# RMP_-_HALF_BRIDGE_0_0_1.net
KiCad netlist of a schematic drawn in EAGLE
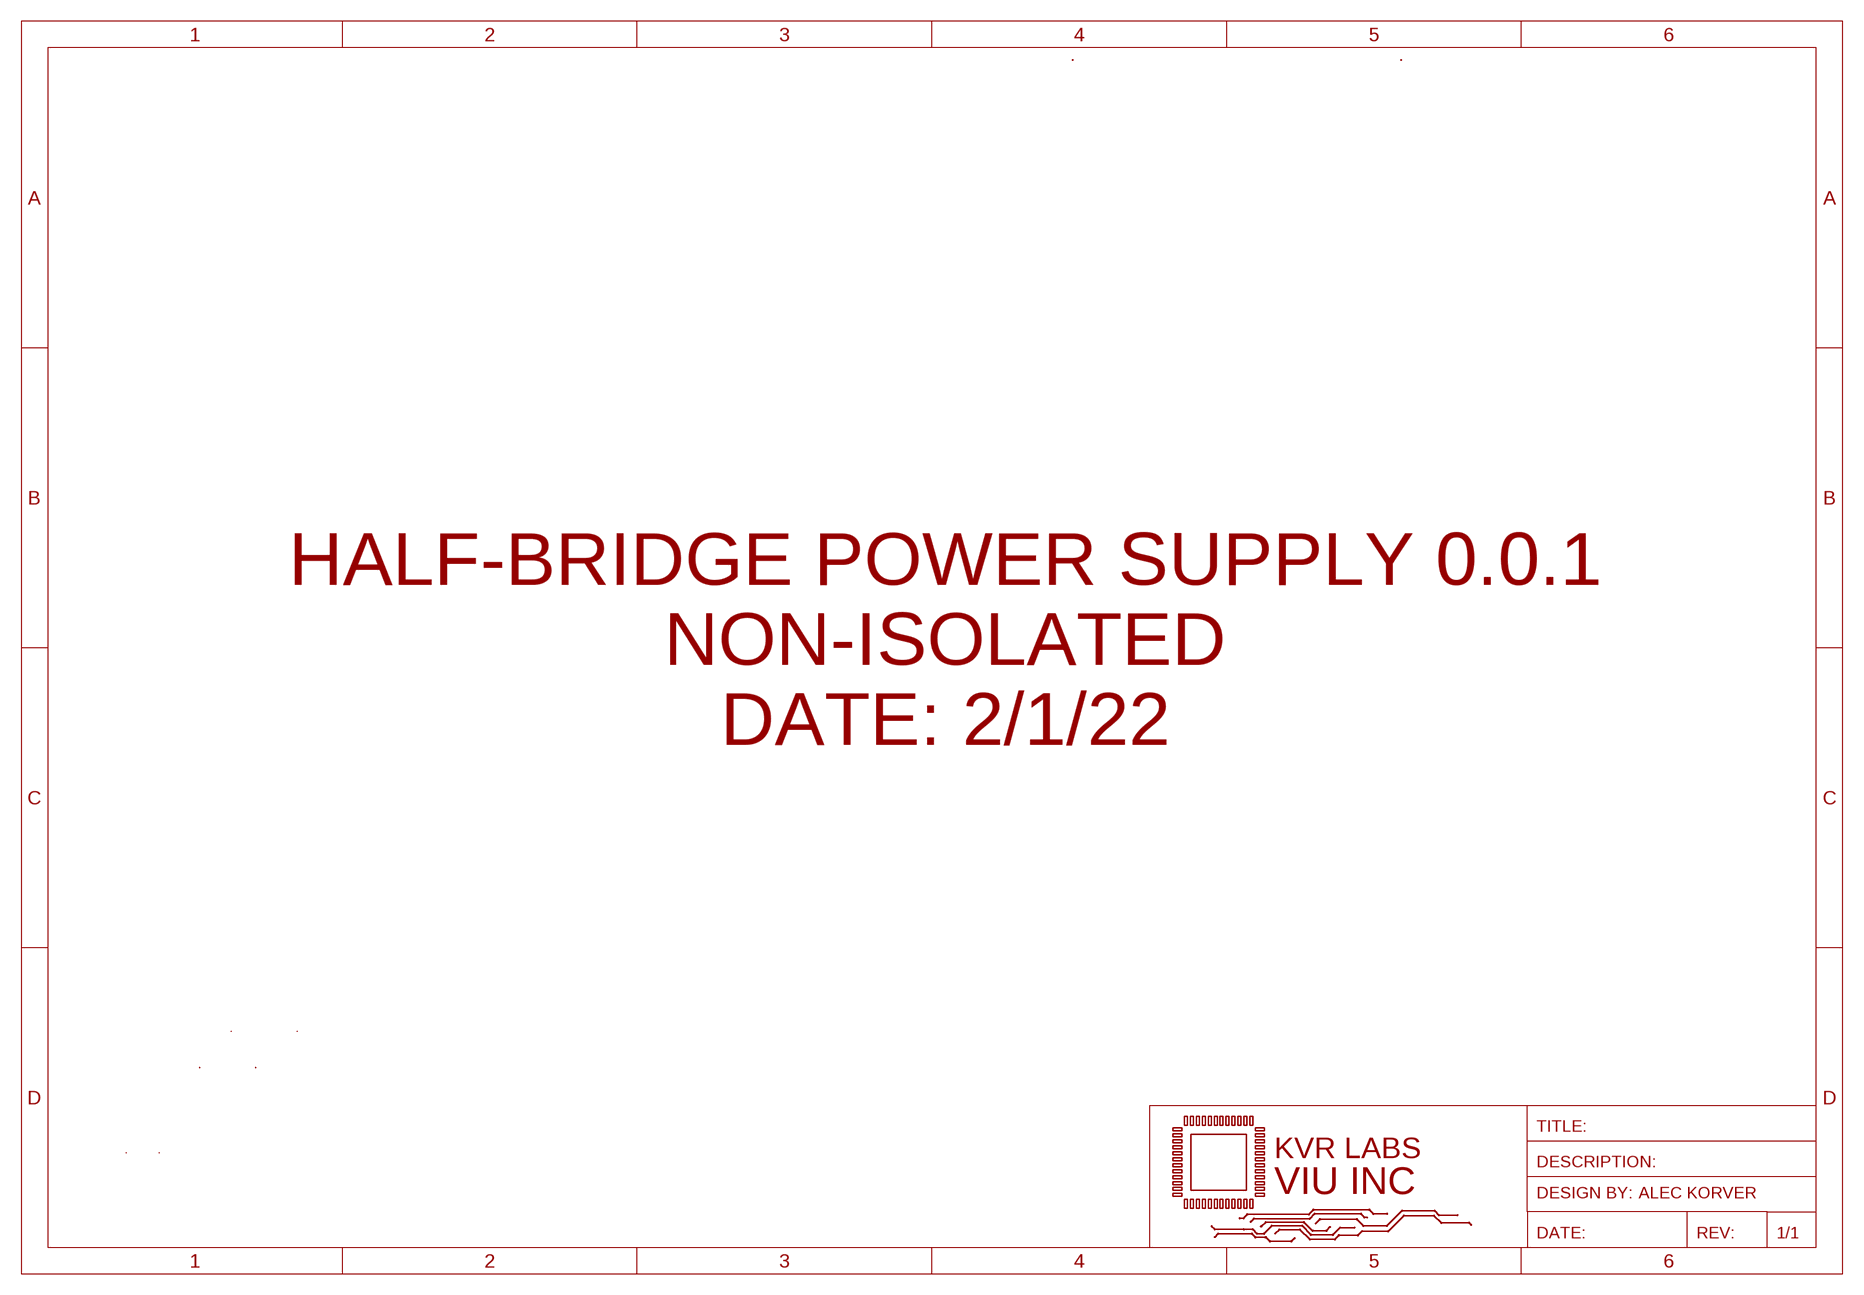
[diagram p0: schematic, sheet 1]
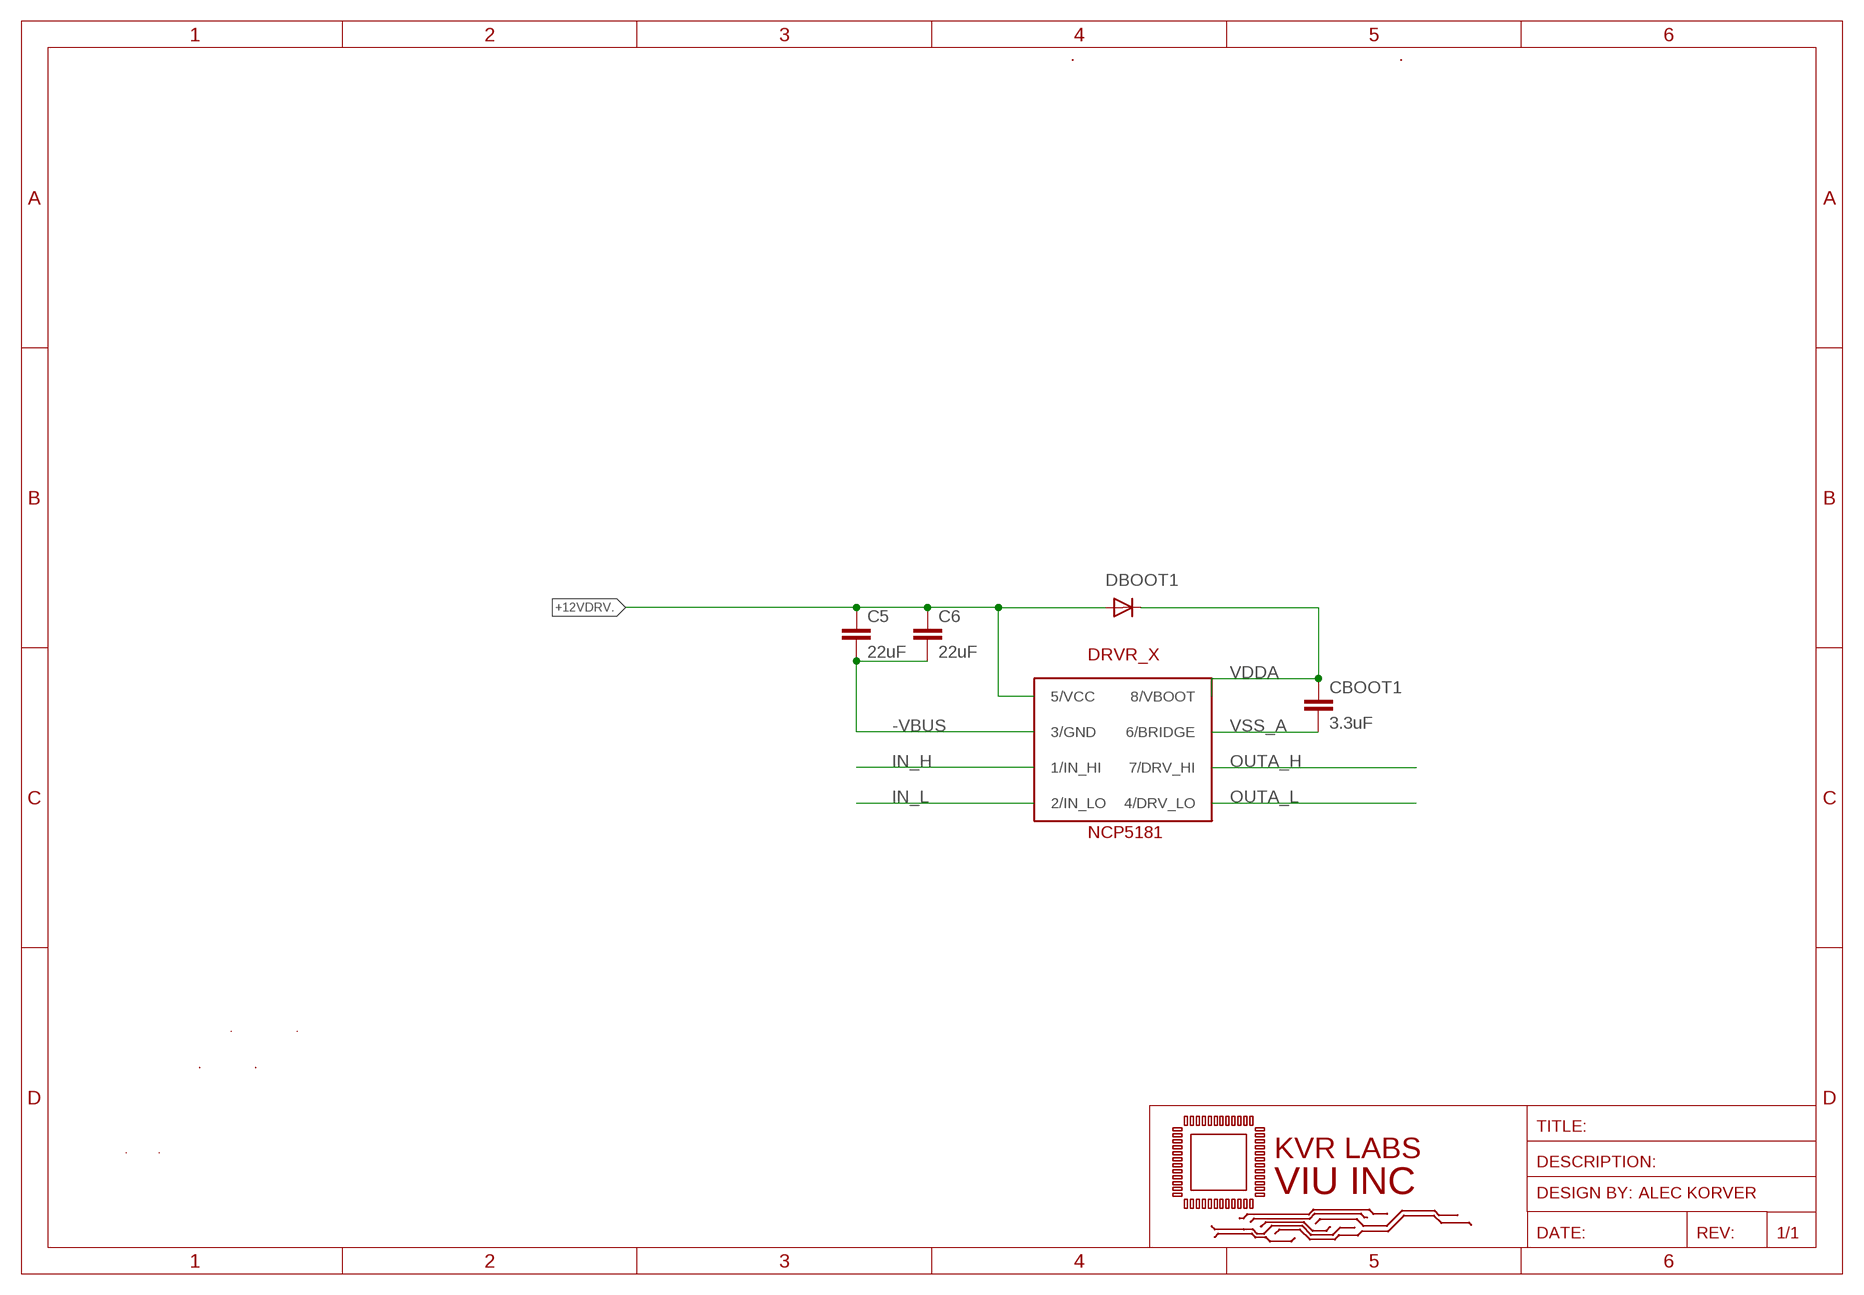
[diagram p1: schematic, sheet 2]
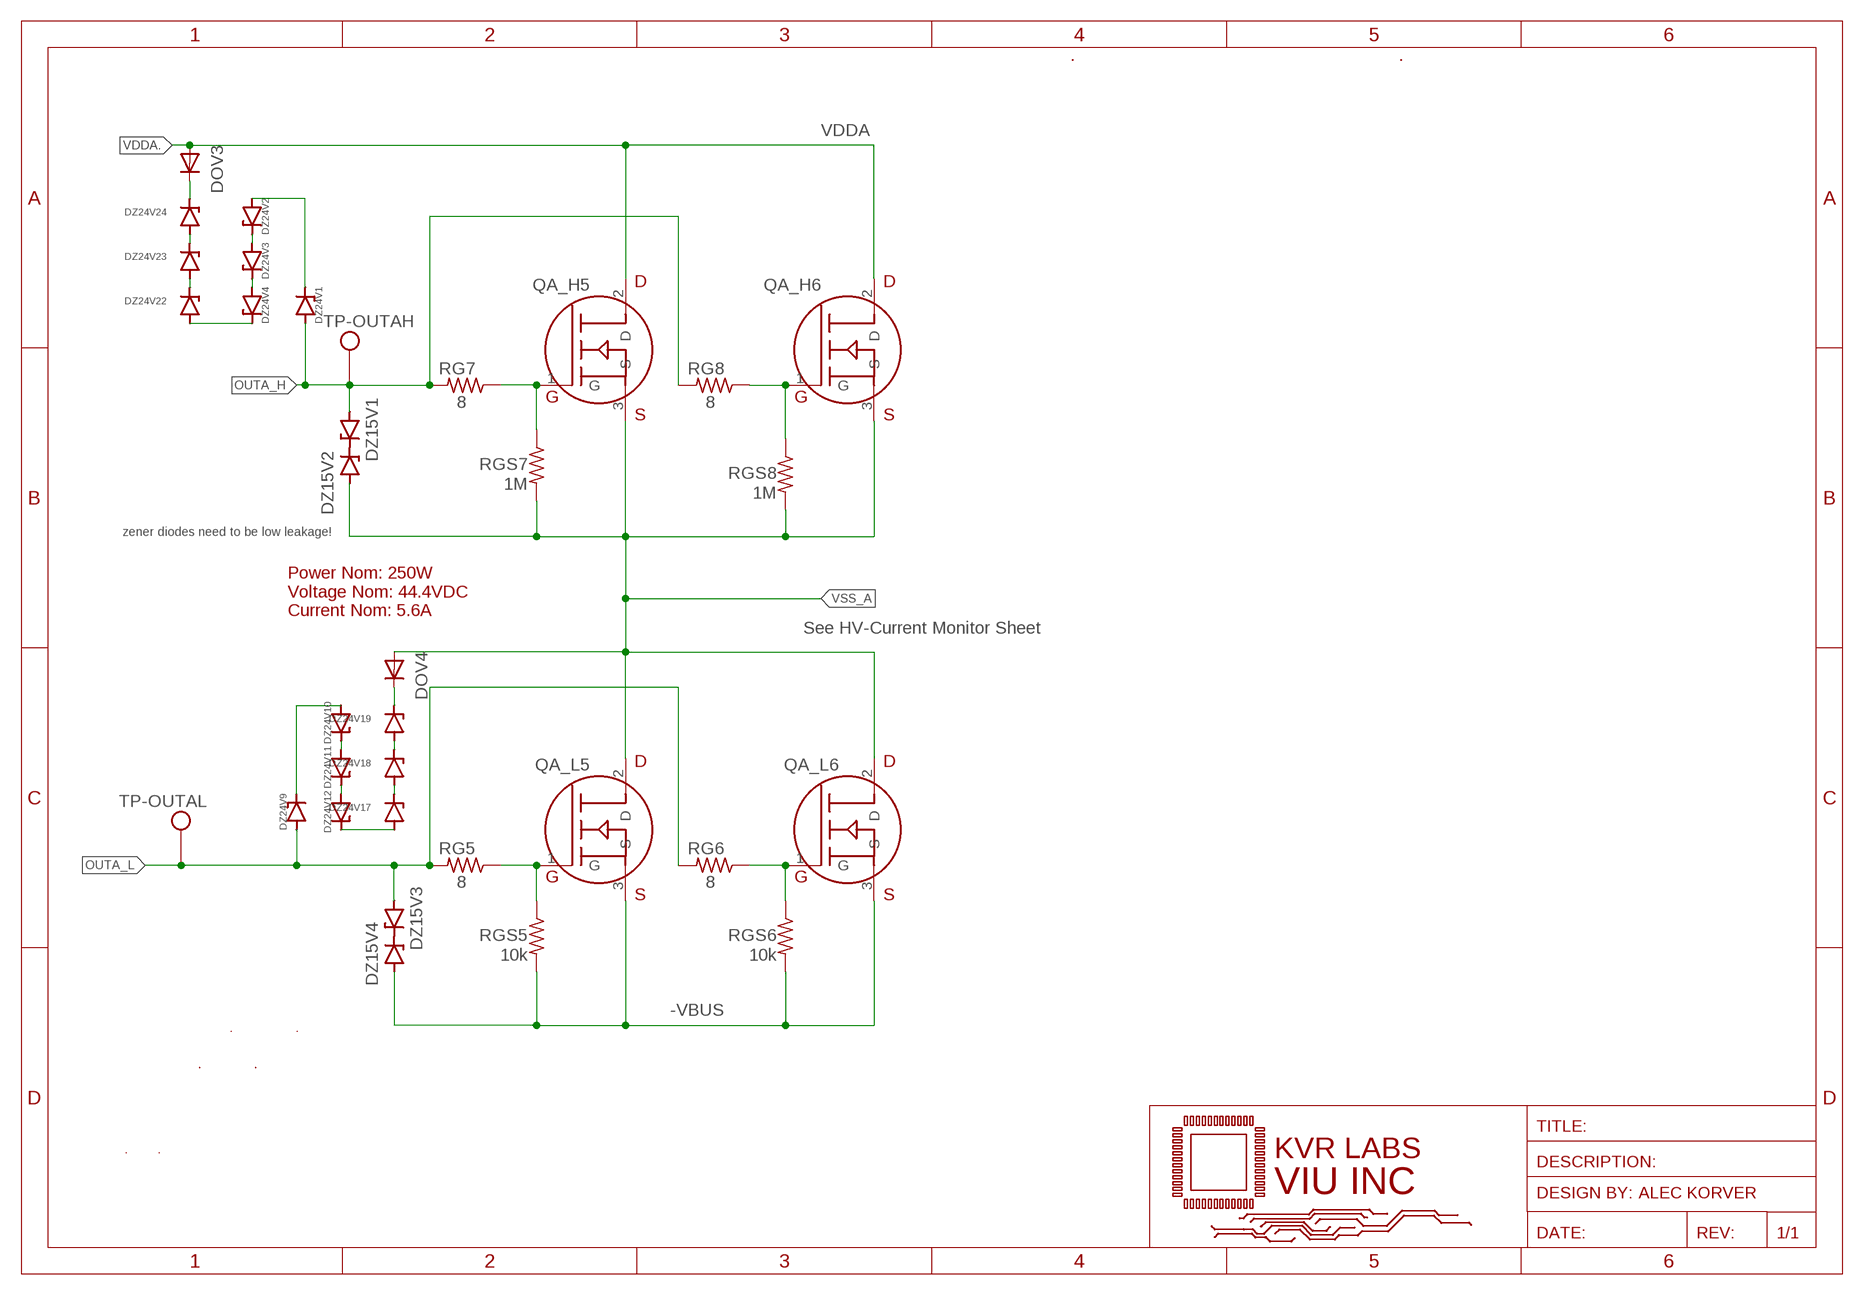
[diagram p2: schematic, sheet 3]
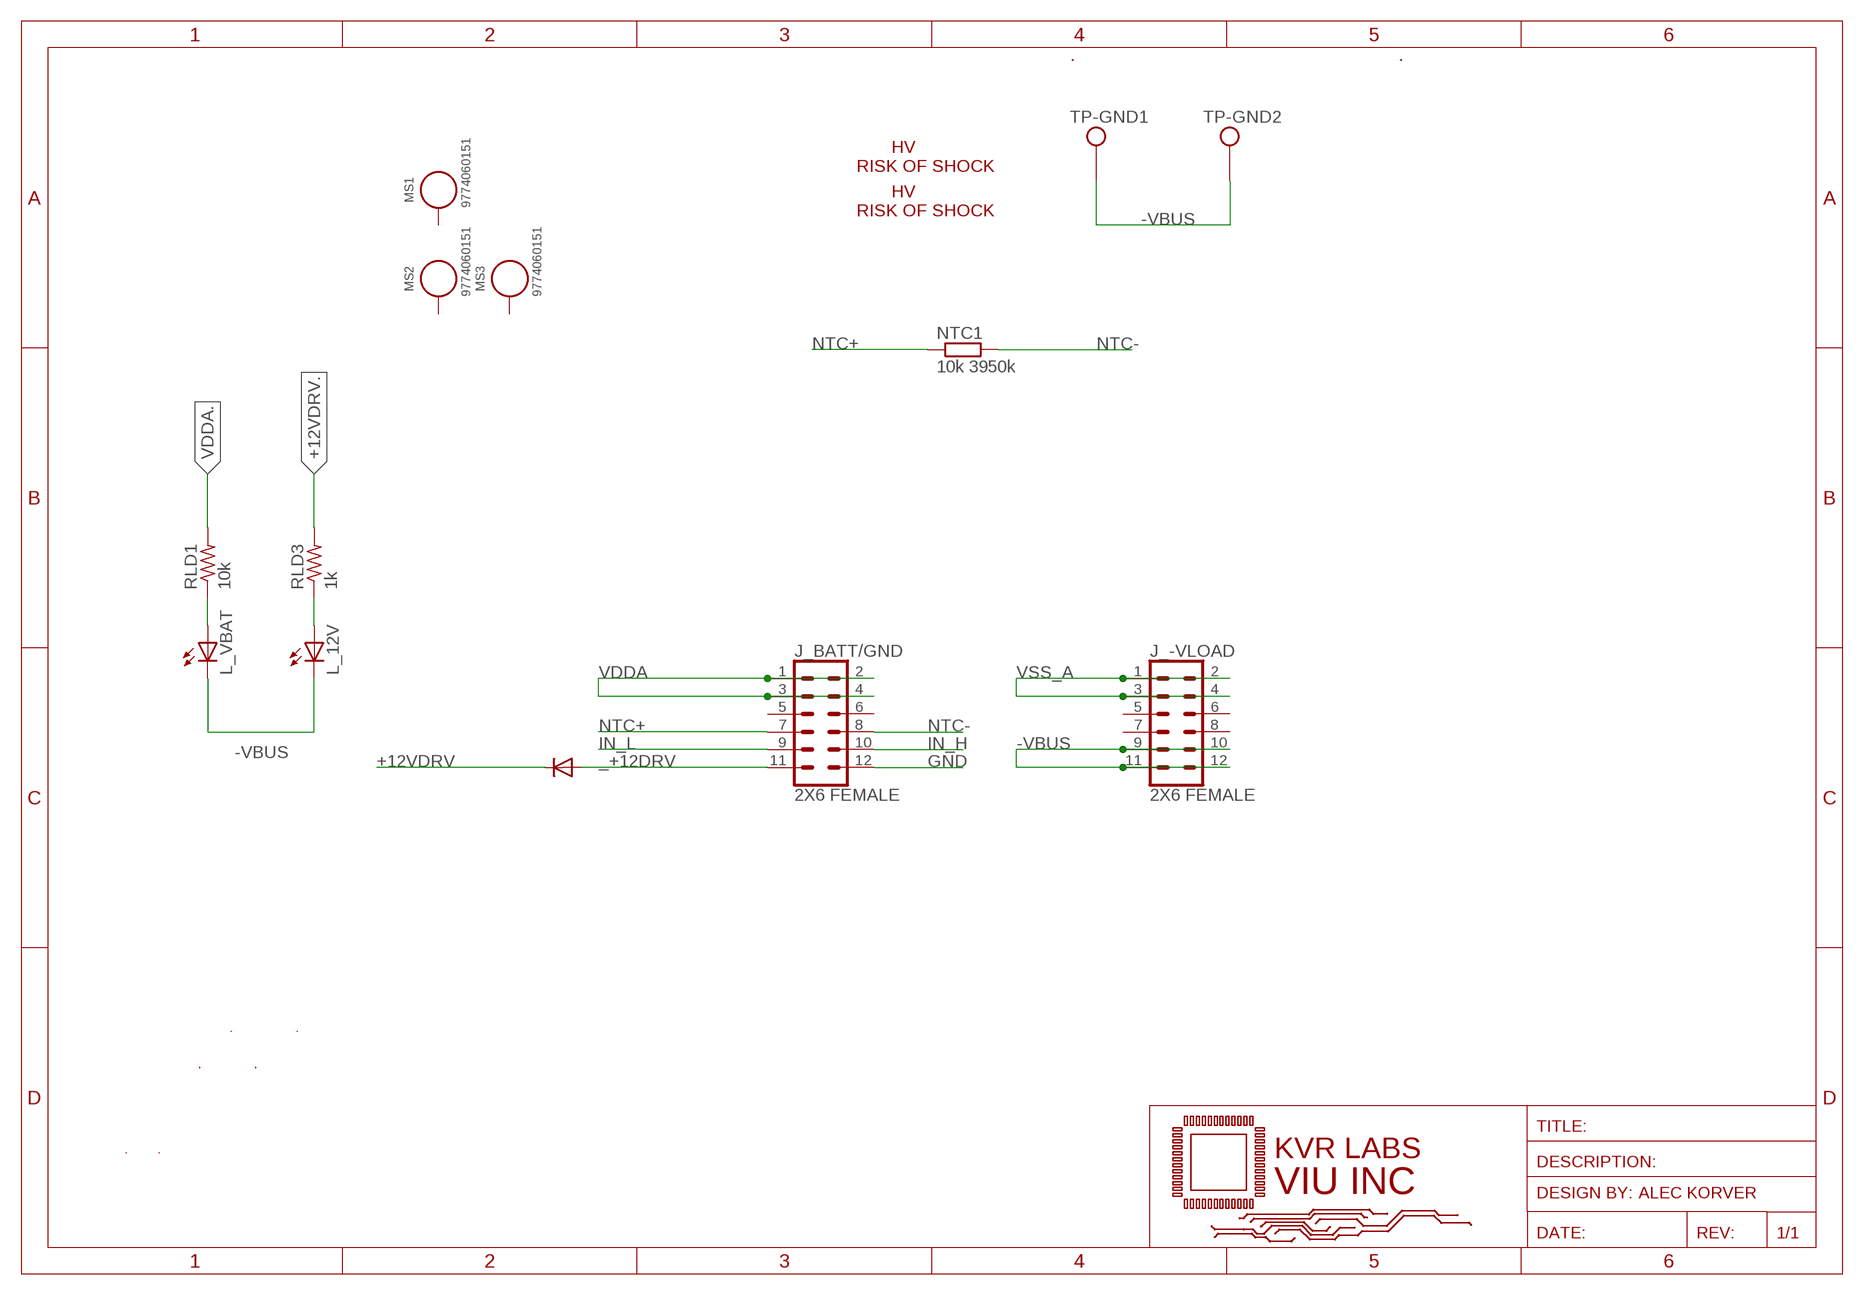
[diagram p3: schematic, sheet 4]
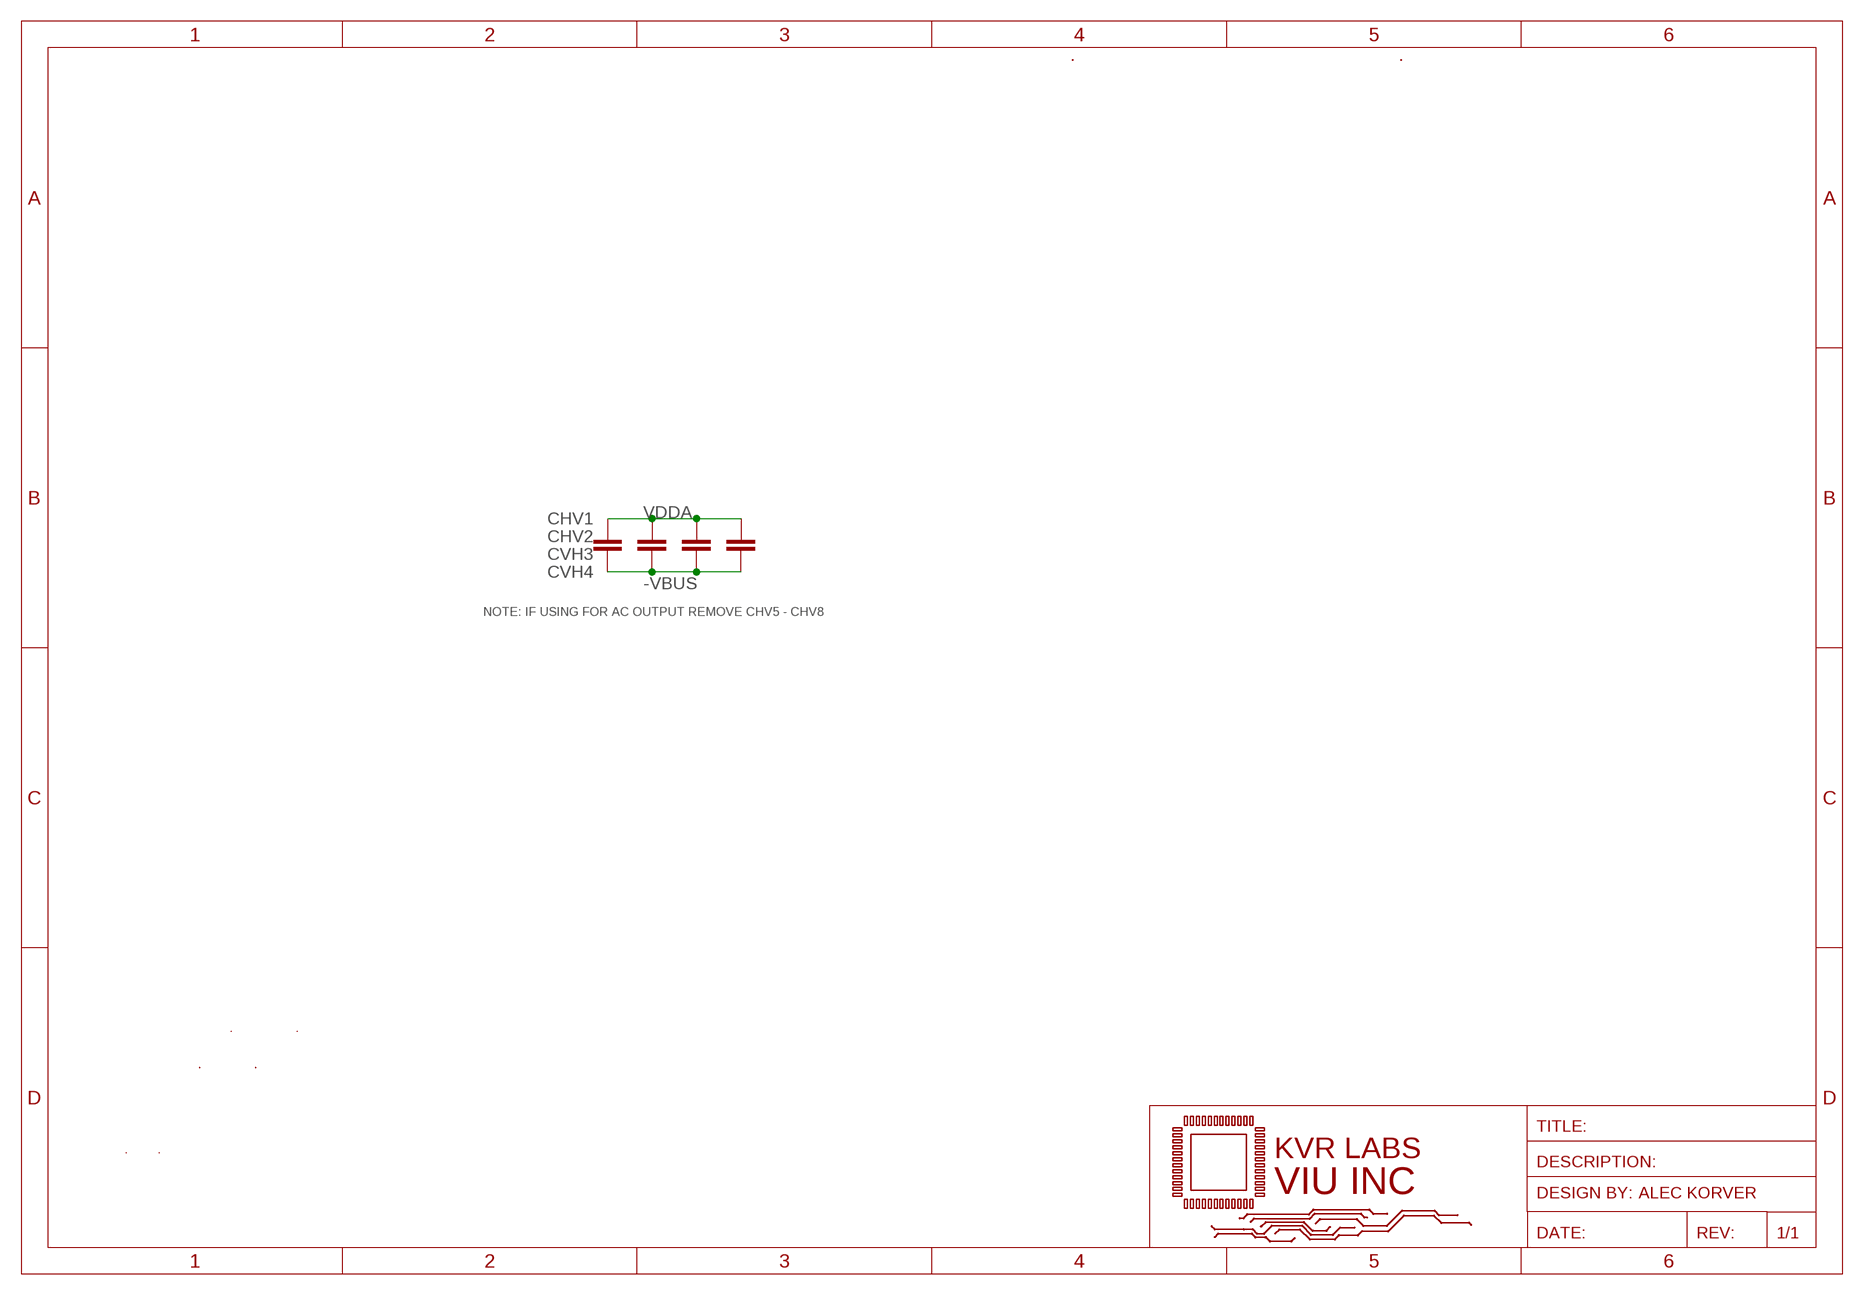
[diagram p4: schematic, sheet 5]

(export (version "E")
  (design (tool "Eeschema 10.0.6"))
  (components
    (comp (ref "C5")
      (value "22uF")
      (footprint "eagle-import:C1206")
      (fields (field (name "LCSC_PART") "C77091"))
      (libsource (lib "eagle-import") (part "C-EUC1206"))
    )
    (comp (ref "C6")
      (value "22uF")
      (footprint "eagle-import:C1206")
      (fields (field (name "LCSC_PART") "C77091"))
      (libsource (lib "eagle-import") (part "C-EUC1206"))
    )
    (comp (ref "CBOOT1")
      (value "3.3uF")
      (footprint "eagle-import:C1812")
      (fields (field (name "LCSC_PART") "C342636"))
      (libsource (lib "eagle-import") (part "C-EUC1812"))
    )
    (comp (ref "DBOOT1")
      (value "DIODESMA")
      (footprint "eagle-import:SMADIODE")
      (fields (field (name "LCSC_PART") "C110531"))
      (libsource (lib "eagle-import") (part "DIODESMA"))
    )
    (comp (ref "DRVR_X")
      (value "NCP5181")
      (footprint "eagle-import:8-SOIC")
      (fields (field (name "LCSC_PART") "DNP"))
      (libsource (lib "eagle-import") (part "NCP5181"))
    )
    (comp (ref "DOV3")
      (value "DIODESMA")
      (footprint "eagle-import:SMADIODE")
      (fields (field (name "LCSC_PART") "C110531"))
      (libsource (lib "eagle-import") (part "DIODESMA"))
    )
    (comp (ref "DOV4")
      (value "DIODESMA")
      (footprint "eagle-import:SMADIODE")
      (fields (field (name "LCSC_PART") "C110531"))
      (libsource (lib "eagle-import") (part "DIODESMA"))
    )
    (comp (ref "DZ15V1")
      (value "NZH15B,115")
      (footprint "eagle-import:SODFL3718X115")
      (fields
        (field (name "MANUFACTURER") "ON Semiconductor ")
        (field (name "MPN") "MMSZ5240BT1G")
        (field (name "LCSC_PART") "C173428")
      )
      (libsource (lib "eagle-import") (part "ZENER_DO-219-AB(SOD123F)MMSZ5240BT"))
    )
    (comp (ref "DZ15V2")
      (value "NZH15B,115")
      (footprint "eagle-import:SODFL3718X115")
      (fields
        (field (name "MANUFACTURER") "ON Semiconductor ")
        (field (name "MPN") "MMSZ5240BT1G")
        (field (name "LCSC_PART") "C173428")
      )
      (libsource (lib "eagle-import") (part "ZENER_DO-219-AB(SOD123F)MMSZ5240BT"))
    )
    (comp (ref "DZ15V3")
      (value "NZH15B,115")
      (footprint "eagle-import:SODFL3718X115")
      (fields
        (field (name "MANUFACTURER") "ON Semiconductor ")
        (field (name "MPN") "MMSZ5240BT1G")
        (field (name "LCSC_PART") "C173428")
      )
      (libsource (lib "eagle-import") (part "ZENER_DO-219-AB(SOD123F)MMSZ5240BT"))
    )
    (comp (ref "DZ15V4")
      (value "NZH15B,115")
      (footprint "eagle-import:SODFL3718X115")
      (fields
        (field (name "MANUFACTURER") "ON Semiconductor ")
        (field (name "MPN") "MMSZ5240BT1G")
        (field (name "LCSC_PART") "C173428")
      )
      (libsource (lib "eagle-import") (part "ZENER_DO-219-AB(SOD123F)MMSZ5240BT"))
    )
    (comp (ref "DZ24V1")
      (value "NZH15B,115")
      (footprint "eagle-import:SODFL3718X115")
      (fields
        (field (name "MANUFACTURER") "ON Semiconductor ")
        (field (name "MPN") "MMSZ5240BT1G")
        (field (name "LCSC_PART") "C266572")
      )
      (libsource (lib "eagle-import") (part "ZENER_DO-219-AB(SOD123F)MMSZ5240BT"))
    )
    (comp (ref "DZ24V2")
      (value "NZH15B,115")
      (footprint "eagle-import:SODFL3718X115")
      (fields
        (field (name "MANUFACTURER") "ON Semiconductor ")
        (field (name "MPN") "MMSZ5240BT1G")
        (field (name "LCSC_PART") "C266572")
      )
      (libsource (lib "eagle-import") (part "ZENER_DO-219-AB(SOD123F)MMSZ5240BT"))
    )
    (comp (ref "DZ24V3")
      (value "NZH15B,115")
      (footprint "eagle-import:SODFL3718X115")
      (fields
        (field (name "MANUFACTURER") "ON Semiconductor ")
        (field (name "MPN") "MMSZ5240BT1G")
        (field (name "LCSC_PART") "C266572")
      )
      (libsource (lib "eagle-import") (part "ZENER_DO-219-AB(SOD123F)MMSZ5240BT"))
    )
    (comp (ref "DZ24V4")
      (value "NZH15B,115")
      (footprint "eagle-import:SODFL3718X115")
      (fields
        (field (name "MANUFACTURER") "ON Semiconductor ")
        (field (name "MPN") "MMSZ5240BT1G")
        (field (name "LCSC_PART") "C266572")
      )
      (libsource (lib "eagle-import") (part "ZENER_DO-219-AB(SOD123F)MMSZ5240BT"))
    )
    (comp (ref "DZ24V9")
      (value "NZH15B,115")
      (footprint "eagle-import:SODFL3718X115")
      (fields
        (field (name "MANUFACTURER") "ON Semiconductor ")
        (field (name "MPN") "MMSZ5240BT1G")
        (field (name "LCSC_PART") "C266572")
      )
      (libsource (lib "eagle-import") (part "ZENER_DO-219-AB(SOD123F)MMSZ5240BT"))
    )
    (comp (ref "DZ24V10")
      (value "NZH15B,115")
      (footprint "eagle-import:SODFL3718X115")
      (fields
        (field (name "MANUFACTURER") "ON Semiconductor ")
        (field (name "MPN") "MMSZ5240BT1G")
        (field (name "LCSC_PART") "C266572")
      )
      (libsource (lib "eagle-import") (part "ZENER_DO-219-AB(SOD123F)MMSZ5240BT"))
    )
    (comp (ref "DZ24V11")
      (value "NZH15B,115")
      (footprint "eagle-import:SODFL3718X115")
      (fields
        (field (name "MANUFACTURER") "ON Semiconductor ")
        (field (name "MPN") "MMSZ5240BT1G")
        (field (name "LCSC_PART") "C266572")
      )
      (libsource (lib "eagle-import") (part "ZENER_DO-219-AB(SOD123F)MMSZ5240BT"))
    )
    (comp (ref "DZ24V12")
      (value "NZH15B,115")
      (footprint "eagle-import:SODFL3718X115")
      (fields
        (field (name "MANUFACTURER") "ON Semiconductor ")
        (field (name "MPN") "MMSZ5240BT1G")
        (field (name "LCSC_PART") "C266572")
      )
      (libsource (lib "eagle-import") (part "ZENER_DO-219-AB(SOD123F)MMSZ5240BT"))
    )
    (comp (ref "DZ24V17")
      (value "NZH15B,115")
      (footprint "eagle-import:SODFL3718X115")
      (fields
        (field (name "MANUFACTURER") "ON Semiconductor ")
        (field (name "MPN") "MMSZ5240BT1G")
        (field (name "LCSC_PART") "C266572")
      )
      (libsource (lib "eagle-import") (part "ZENER_DO-219-AB(SOD123F)MMSZ5240BT"))
    )
    (comp (ref "DZ24V18")
      (value "NZH15B,115")
      (footprint "eagle-import:SODFL3718X115")
      (fields
        (field (name "MANUFACTURER") "ON Semiconductor ")
        (field (name "MPN") "MMSZ5240BT1G")
        (field (name "LCSC_PART") "C266572")
      )
      (libsource (lib "eagle-import") (part "ZENER_DO-219-AB(SOD123F)MMSZ5240BT"))
    )
    (comp (ref "DZ24V19")
      (value "NZH15B,115")
      (footprint "eagle-import:SODFL3718X115")
      (fields
        (field (name "MANUFACTURER") "ON Semiconductor ")
        (field (name "MPN") "MMSZ5240BT1G")
        (field (name "LCSC_PART") "C266572")
      )
      (libsource (lib "eagle-import") (part "ZENER_DO-219-AB(SOD123F)MMSZ5240BT"))
    )
    (comp (ref "DZ24V22")
      (value "NZH15B,115")
      (footprint "eagle-import:SODFL3718X115")
      (fields
        (field (name "MANUFACTURER") "ON Semiconductor ")
        (field (name "MPN") "MMSZ5240BT1G")
        (field (name "LCSC_PART") "C266572")
      )
      (libsource (lib "eagle-import") (part "ZENER_DO-219-AB(SOD123F)MMSZ5240BT"))
    )
    (comp (ref "DZ24V23")
      (value "NZH15B,115")
      (footprint "eagle-import:SODFL3718X115")
      (fields
        (field (name "MANUFACTURER") "ON Semiconductor ")
        (field (name "MPN") "MMSZ5240BT1G")
        (field (name "LCSC_PART") "C266572")
      )
      (libsource (lib "eagle-import") (part "ZENER_DO-219-AB(SOD123F)MMSZ5240BT"))
    )
    (comp (ref "DZ24V24")
      (value "NZH15B,115")
      (footprint "eagle-import:SODFL3718X115")
      (fields
        (field (name "MANUFACTURER") "ON Semiconductor ")
        (field (name "MPN") "MMSZ5240BT1G")
        (field (name "LCSC_PART") "C266572")
      )
      (libsource (lib "eagle-import") (part "ZENER_DO-219-AB(SOD123F)MMSZ5240BT"))
    )
    (comp (ref "QA_H5")
      (value "IPB60R060P7ATMA1")
      (footprint "eagle-import:D2PACK")
      (fields (field (name "LCSC_PART") "DNP"))
      (libsource (lib "eagle-import") (part "IPB60R060P7ATMA1"))
    )
    (comp (ref "QA_H6")
      (value "IPB60R060P7ATMA1")
      (footprint "eagle-import:D2PACK")
      (fields (field (name "LCSC_PART") "DNP"))
      (libsource (lib "eagle-import") (part "IPB60R060P7ATMA1"))
    )
    (comp (ref "QA_L5")
      (value "IPB60R060P7ATMA1")
      (footprint "eagle-import:D2PACK")
      (fields (field (name "LCSC_PART") "DNP"))
      (libsource (lib "eagle-import") (part "IPB60R060P7ATMA1"))
    )
    (comp (ref "QA_L6")
      (value "IPB60R060P7ATMA1")
      (footprint "eagle-import:D2PACK")
      (fields (field (name "LCSC_PART") "DNP"))
      (libsource (lib "eagle-import") (part "IPB60R060P7ATMA1"))
    )
    (comp (ref "RG5")
      (value "8")
      (footprint "eagle-import:R1206")
      (fields (field (name "LCSC_PART") "C118070"))
      (libsource (lib "eagle-import") (part "R-US_R1206"))
    )
    (comp (ref "RG6")
      (value "8")
      (footprint "eagle-import:R1206")
      (fields (field (name "LCSC_PART") "C118070"))
      (libsource (lib "eagle-import") (part "R-US_R1206"))
    )
    (comp (ref "RG7")
      (value "8")
      (footprint "eagle-import:R1206")
      (fields (field (name "LCSC_PART") "C118070"))
      (libsource (lib "eagle-import") (part "R-US_R1206"))
    )
    (comp (ref "RG8")
      (value "8")
      (footprint "eagle-import:R1206")
      (fields (field (name "LCSC_PART") "C118070"))
      (libsource (lib "eagle-import") (part "R-US_R1206"))
    )
    (comp (ref "RGS5")
      (value "10k")
      (footprint "eagle-import:R1206")
      (fields (field (name "LCSC_PART") "C140407"))
      (libsource (lib "eagle-import") (part "R-US_R1206"))
    )
    (comp (ref "RGS6")
      (value "10k")
      (footprint "eagle-import:R1206")
      (fields (field (name "LCSC_PART") "C140407"))
      (libsource (lib "eagle-import") (part "R-US_R1206"))
    )
    (comp (ref "RGS7")
      (value "1M")
      (footprint "eagle-import:R1206")
      (fields (field (name "LCSC_PART") "C105578"))
      (libsource (lib "eagle-import") (part "R-US_R1206"))
    )
    (comp (ref "RGS8")
      (value "1M")
      (footprint "eagle-import:R1206")
      (fields (field (name "LCSC_PART") "C105578"))
      (libsource (lib "eagle-import") (part "R-US_R1206"))
    )
    (comp (ref "TP-OUTAH")
      (value "THM_TESTPOINT_5000_SERIES")
      (footprint "eagle-import:THM-TESTPOINT")
      (fields (field (name "LCSC_PART") "DNP"))
      (libsource (lib "eagle-import") (part "THM_TESTPOINT_5000_SERIES"))
    )
    (comp (ref "TP-OUTAL")
      (value "THM_TESTPOINT_5000_SERIES")
      (footprint "eagle-import:THM-TESTPOINT")
      (fields (field (name "LCSC_PART") "DNP"))
      (libsource (lib "eagle-import") (part "THM_TESTPOINT_5000_SERIES"))
    )
    (comp (ref "D12IN")
      (value "DIODESMA")
      (footprint "eagle-import:SMADIODE")
      (fields (field (name "LCSC_PART") "C110531"))
      (libsource (lib "eagle-import") (part "DIODESMA"))
    )
    (comp (ref "J_-VLOAD")
      (value "2X6 FEMALE")
      (footprint "eagle-import:2X6")
      (fields (field (name "LCSC_PART") "DNP"))
      (libsource (lib "eagle-import") (part "CONN_06X2PTH_FEMALE"))
    )
    (comp (ref "J_BATT/GND")
      (value "2X6 FEMALE")
      (footprint "eagle-import:2X6")
      (fields (field (name "LCSC_PART") "DNP"))
      (libsource (lib "eagle-import") (part "CONN_06X2PTH_FEMALE"))
    )
    (comp (ref "L_12V")
      (value "LEDCHIPLED_1206")
      (footprint "eagle-import:CHIPLED_1206")
      (fields (field (name "LCSC_PART") "C434439"))
      (libsource (lib "eagle-import") (part "LEDCHIPLED_1206"))
    )
    (comp (ref "L_VBAT")
      (value "LEDCHIPLED_1206")
      (footprint "eagle-import:CHIPLED_1206")
      (fields (field (name "LCSC_PART") "C434439"))
      (libsource (lib "eagle-import") (part "LEDCHIPLED_1206"))
    )
    (comp (ref "MS1")
      (value "9774060151")
      (footprint "eagle-import:WA-SMSI_9774060151")
      (fields (field (name "LCSC_PART") "DNP"))
      (libsource (lib "eagle-import") (part "WA-SMSI_9774XXX151_9774060151"))
    )
    (comp (ref "MS2")
      (value "9774060151")
      (footprint "eagle-import:WA-SMSI_9774060151")
      (fields (field (name "LCSC_PART") "DNP"))
      (libsource (lib "eagle-import") (part "WA-SMSI_9774XXX151_9774060151"))
    )
    (comp (ref "MS3")
      (value "9774060151")
      (footprint "eagle-import:WA-SMSI_9774060151")
      (fields (field (name "LCSC_PART") "DNP"))
      (libsource (lib "eagle-import") (part "WA-SMSI_9774XXX151_9774060151"))
    )
    (comp (ref "NTC1")
      (value "10k 3950k")
      (footprint "eagle-import:R0805")
      (fields (field (name "LCSC_PART") "C95968"))
      (libsource (lib "eagle-import") (part "R-EU_R0805"))
    )
    (comp (ref "RLD1")
      (value "10k")
      (footprint "eagle-import:R1206")
      (fields (field (name "LCSC_PART") "C140407"))
      (libsource (lib "eagle-import") (part "R-US_R1206"))
    )
    (comp (ref "RLD3")
      (value "1k")
      (footprint "eagle-import:R1206")
      (fields (field (name "LCSC_PART") "C115421"))
      (libsource (lib "eagle-import") (part "R-US_R1206"))
    )
    (comp (ref "TP-GND1")
      (value "THM_TESTPOINT_5000_SERIES")
      (footprint "eagle-import:THM-TESTPOINT")
      (fields (field (name "LCSC_PART") "DNP"))
      (libsource (lib "eagle-import") (part "THM_TESTPOINT_5000_SERIES"))
    )
    (comp (ref "TP-GND2")
      (value "THM_TESTPOINT_5000_SERIES")
      (footprint "eagle-import:THM-TESTPOINT")
      (fields (field (name "LCSC_PART") "DNP"))
      (libsource (lib "eagle-import") (part "THM_TESTPOINT_5000_SERIES"))
    )
    (comp (ref "U$10")
      (value "ELECTRIC_SHOCK")
      (footprint "eagle-import:ELECTRIC_SHOCK")
      (fields (field (name "LCSC_PART") "DNP"))
      (libsource (lib "eagle-import") (part "ELECTRIC_SHOCK"))
    )
    (comp (ref "U$11")
      (value "ELECTRIC_SHOCK")
      (footprint "eagle-import:ELECTRIC_SHOCK")
      (fields (field (name "LCSC_PART") "DNP"))
      (libsource (lib "eagle-import") (part "ELECTRIC_SHOCK"))
    )
    (comp (ref "CHV1")
      (value "3.3uF, 100V")
      (footprint "eagle-import:C2220K")
      (fields (field (name "LCSC_PART") "C342270"))
      (libsource (lib "eagle-import") (part "C-EUC2220K"))
    )
    (comp (ref "CHV2")
      (value "3.3uF, 100V")
      (footprint "eagle-import:C2220K")
      (fields (field (name "LCSC_PART") "C342270"))
      (libsource (lib "eagle-import") (part "C-EUC2220K"))
    )
    (comp (ref "CVH3")
      (value "3.3uF, 100V")
      (footprint "eagle-import:C2220K")
      (fields (field (name "LCSC_PART") "C342270"))
      (libsource (lib "eagle-import") (part "C-EUC2220K"))
    )
    (comp (ref "CVH4")
      (value "3.3uF, 100V")
      (footprint "eagle-import:C2220K")
      (fields (field (name "LCSC_PART") "C342270"))
      (libsource (lib "eagle-import") (part "C-EUC2220K"))
    )
  )
  (nets
    (net (code "1") (name "+12VDRV") (class "Default")
      (node (ref "C5") (pin "1") (pinfunction "1_1") (pintype "passive"))
      (node (ref "C6") (pin "1") (pinfunction "1_1") (pintype "passive"))
      (node (ref "D12IN") (pin "C") (pinfunction "C_C") (pintype "passive"))
      (node (ref "DBOOT1") (pin "A") (pinfunction "A_A") (pintype "passive"))
      (node (ref "DRVR_X") (pin "5") (pinfunction "5/VCC_5") (pintype "bidirectional"))
      (node (ref "RLD3") (pin "2") (pinfunction "2_2") (pintype "passive"))
    )
    (net (code "2") (name "-VBUS") (class "Default")
      (node (ref "C5") (pin "2") (pinfunction "2_2") (pintype "passive"))
      (node (ref "C6") (pin "2") (pinfunction "2_2") (pintype "passive"))
      (node (ref "CHV1") (pin "2") (pinfunction "2_2") (pintype "passive"))
      (node (ref "CHV2") (pin "2") (pinfunction "2_2") (pintype "passive"))
      (node (ref "CVH3") (pin "2") (pinfunction "2_2") (pintype "passive"))
      (node (ref "CVH4") (pin "2") (pinfunction "2_2") (pintype "passive"))
      (node (ref "DRVR_X") (pin "3") (pinfunction "3/GND_3") (pintype "bidirectional"))
      (node (ref "DZ15V4") (pin "2") (pinfunction "A_2") (pintype "passive"))
      (node (ref "J_-VLOAD") (pin "10") (pinfunction "10_10") (pintype "passive"))
      (node (ref "J_-VLOAD") (pin "11") (pinfunction "11_11") (pintype "passive"))
      (node (ref "J_-VLOAD") (pin "12") (pinfunction "12_12") (pintype "passive"))
      (node (ref "J_-VLOAD") (pin "9") (pinfunction "9_9") (pintype "passive"))
      (node (ref "L_12V") (pin "C") (pinfunction "C_C") (pintype "passive"))
      (node (ref "L_VBAT") (pin "C") (pinfunction "C_C") (pintype "passive"))
      (node (ref "QA_L5") (pin "3") (pinfunction "S_3") (pintype "bidirectional"))
      (node (ref "QA_L6") (pin "3") (pinfunction "S_3") (pintype "bidirectional"))
      (node (ref "RGS5") (pin "2") (pinfunction "2_2") (pintype "passive"))
      (node (ref "RGS6") (pin "2") (pinfunction "2_2") (pintype "passive"))
      (node (ref "TP-GND1") (pin "P1") (pinfunction "P$1_P1") (pintype "bidirectional"))
      (node (ref "TP-GND2") (pin "P1") (pinfunction "P$1_P1") (pintype "bidirectional"))
    )
    (net (code "3") (name "GND") (class "Default")
      (node (ref "J_BATT/GND") (pin "12") (pinfunction "12_12") (pintype "passive"))
    )
    (net (code "4") (name "IN_H") (class "Default")
      (node (ref "DRVR_X") (pin "1") (pinfunction "1/IN_HI_1") (pintype "bidirectional"))
      (node (ref "J_BATT/GND") (pin "10") (pinfunction "10_10") (pintype "passive"))
    )
    (net (code "5") (name "IN_L") (class "Default")
      (node (ref "DRVR_X") (pin "2") (pinfunction "2/IN_LO_2") (pintype "bidirectional"))
      (node (ref "J_BATT/GND") (pin "9") (pinfunction "9_9") (pintype "passive"))
    )
    (net (code "6") (name "NTC+") (class "Default")
      (node (ref "J_BATT/GND") (pin "7") (pinfunction "7_7") (pintype "passive"))
      (node (ref "NTC1") (pin "1") (pinfunction "1_1") (pintype "passive"))
    )
    (net (code "7") (name "NTC-") (class "Default")
      (node (ref "J_BATT/GND") (pin "8") (pinfunction "8_8") (pintype "passive"))
      (node (ref "NTC1") (pin "2") (pinfunction "2_2") (pintype "passive"))
    )
    (net (code "8") (name "Net-(DZ15V1-C)") (class "Default")
      (node (ref "DZ15V1") (pin "1") (pinfunction "C_1") (pintype "passive"))
      (node (ref "DZ15V2") (pin "1") (pinfunction "C_1") (pintype "passive"))
    )
    (net (code "9") (name "Net-(DZ15V3-C)") (class "Default")
      (node (ref "DZ15V3") (pin "1") (pinfunction "C_1") (pintype "passive"))
      (node (ref "DZ15V4") (pin "1") (pinfunction "C_1") (pintype "passive"))
    )
    (net (code "10") (name "Net-(DZ24V1-C)") (class "Default")
      (node (ref "DZ24V1") (pin "1") (pinfunction "C_1") (pintype "passive"))
      (node (ref "DZ24V2") (pin "2") (pinfunction "A_2") (pintype "passive"))
    )
    (net (code "11") (name "Net-(DZ24V2-C)") (class "Default")
      (node (ref "DZ24V2") (pin "1") (pinfunction "C_1") (pintype "passive"))
      (node (ref "DZ24V3") (pin "2") (pinfunction "A_2") (pintype "passive"))
    )
    (net (code "12") (name "Net-(DZ24V3-C)") (class "Default")
      (node (ref "DZ24V3") (pin "1") (pinfunction "C_1") (pintype "passive"))
      (node (ref "DZ24V4") (pin "2") (pinfunction "A_2") (pintype "passive"))
    )
    (net (code "13") (name "Net-(DZ24V10-A)") (class "Default")
      (node (ref "DZ24V10") (pin "2") (pinfunction "A_2") (pintype "passive"))
      (node (ref "DZ24V9") (pin "1") (pinfunction "C_1") (pintype "passive"))
    )
    (net (code "14") (name "Net-(DZ24V10-C)") (class "Default")
      (node (ref "DZ24V10") (pin "1") (pinfunction "C_1") (pintype "passive"))
      (node (ref "DZ24V11") (pin "2") (pinfunction "A_2") (pintype "passive"))
    )
    (net (code "15") (name "Net-(DZ24V11-C)") (class "Default")
      (node (ref "DZ24V11") (pin "1") (pinfunction "C_1") (pintype "passive"))
      (node (ref "DZ24V12") (pin "2") (pinfunction "A_2") (pintype "passive"))
    )
    (net (code "16") (name "Net-(DZ24V12-C)") (class "Default")
      (node (ref "DZ24V12") (pin "1") (pinfunction "C_1") (pintype "passive"))
      (node (ref "DZ24V17") (pin "2") (pinfunction "A_2") (pintype "passive"))
    )
    (net (code "17") (name "Net-(DZ24V17-C)") (class "Default")
      (node (ref "DZ24V17") (pin "1") (pinfunction "C_1") (pintype "passive"))
      (node (ref "DZ24V18") (pin "2") (pinfunction "A_2") (pintype "passive"))
    )
    (net (code "18") (name "Net-(DZ24V18-C)") (class "Default")
      (node (ref "DZ24V18") (pin "1") (pinfunction "C_1") (pintype "passive"))
      (node (ref "DZ24V19") (pin "2") (pinfunction "A_2") (pintype "passive"))
    )
    (net (code "19") (name "Net-(DZ24V19-C)") (class "Default")
      (node (ref "DOV4") (pin "C") (pinfunction "C_C") (pintype "passive"))
      (node (ref "DZ24V19") (pin "1") (pinfunction "C_1") (pintype "passive"))
    )
    (net (code "20") (name "Net-(DZ24V22-A)") (class "Default")
      (node (ref "DZ24V22") (pin "2") (pinfunction "A_2") (pintype "passive"))
      (node (ref "DZ24V4") (pin "1") (pinfunction "C_1") (pintype "passive"))
    )
    (net (code "21") (name "Net-(DZ24V22-C)") (class "Default")
      (node (ref "DZ24V22") (pin "1") (pinfunction "C_1") (pintype "passive"))
      (node (ref "DZ24V23") (pin "2") (pinfunction "A_2") (pintype "passive"))
    )
    (net (code "22") (name "Net-(DZ24V23-C)") (class "Default")
      (node (ref "DZ24V23") (pin "1") (pinfunction "C_1") (pintype "passive"))
      (node (ref "DZ24V24") (pin "2") (pinfunction "A_2") (pintype "passive"))
    )
    (net (code "23") (name "Net-(DZ24V24-C)") (class "Default")
      (node (ref "DOV3") (pin "C") (pinfunction "C_C") (pintype "passive"))
      (node (ref "DZ24V24") (pin "1") (pinfunction "C_1") (pintype "passive"))
    )
    (net (code "24") (name "Net-(L_12V-PadA)") (class "Default")
      (node (ref "L_12V") (pin "A") (pinfunction "A_A") (pintype "passive"))
      (node (ref "RLD3") (pin "1") (pinfunction "1_1") (pintype "passive"))
    )
    (net (code "25") (name "Net-(L_VBAT-PadA)") (class "Default")
      (node (ref "L_VBAT") (pin "A") (pinfunction "A_A") (pintype "passive"))
      (node (ref "RLD1") (pin "1") (pinfunction "1_1") (pintype "passive"))
    )
    (net (code "26") (name "Net-(QA_H5-G)") (class "Default")
      (node (ref "QA_H5") (pin "1") (pinfunction "G_1") (pintype "bidirectional"))
      (node (ref "RG7") (pin "1") (pinfunction "1_1") (pintype "passive"))
      (node (ref "RGS7") (pin "1") (pinfunction "1_1") (pintype "passive"))
    )
    (net (code "27") (name "Net-(QA_H6-G)") (class "Default")
      (node (ref "QA_H6") (pin "1") (pinfunction "G_1") (pintype "bidirectional"))
      (node (ref "RG8") (pin "1") (pinfunction "1_1") (pintype "passive"))
      (node (ref "RGS8") (pin "1") (pinfunction "1_1") (pintype "passive"))
    )
    (net (code "28") (name "Net-(QA_L5-G)") (class "Default")
      (node (ref "QA_L5") (pin "1") (pinfunction "G_1") (pintype "bidirectional"))
      (node (ref "RG5") (pin "1") (pinfunction "1_1") (pintype "passive"))
      (node (ref "RGS5") (pin "1") (pinfunction "1_1") (pintype "passive"))
    )
    (net (code "29") (name "Net-(QA_L6-G)") (class "Default")
      (node (ref "QA_L6") (pin "1") (pinfunction "G_1") (pintype "bidirectional"))
      (node (ref "RG6") (pin "1") (pinfunction "1_1") (pintype "passive"))
      (node (ref "RGS6") (pin "1") (pinfunction "1_1") (pintype "passive"))
    )
    (net (code "30") (name "OUTA_H") (class "Default")
      (node (ref "DRVR_X") (pin "7") (pinfunction "7/DRV_HI_7") (pintype "bidirectional"))
      (node (ref "DZ15V1") (pin "2") (pinfunction "A_2") (pintype "passive"))
      (node (ref "DZ24V1") (pin "2") (pinfunction "A_2") (pintype "passive"))
      (node (ref "RG7") (pin "2") (pinfunction "2_2") (pintype "passive"))
      (node (ref "RG8") (pin "2") (pinfunction "2_2") (pintype "passive"))
      (node (ref "TP-OUTAH") (pin "P1") (pinfunction "P$1_P1") (pintype "bidirectional"))
    )
    (net (code "31") (name "OUTA_L") (class "Default")
      (node (ref "DRVR_X") (pin "4") (pinfunction "4/DRV_LO_4") (pintype "bidirectional"))
      (node (ref "DZ15V3") (pin "2") (pinfunction "A_2") (pintype "passive"))
      (node (ref "DZ24V9") (pin "2") (pinfunction "A_2") (pintype "passive"))
      (node (ref "RG5") (pin "2") (pinfunction "2_2") (pintype "passive"))
      (node (ref "RG6") (pin "2") (pinfunction "2_2") (pintype "passive"))
      (node (ref "TP-OUTAL") (pin "P1") (pinfunction "P$1_P1") (pintype "bidirectional"))
    )
    (net (code "32") (name "VDDA") (class "Default")
      (node (ref "CBOOT1") (pin "1") (pinfunction "1_1") (pintype "passive"))
      (node (ref "CHV1") (pin "1") (pinfunction "1_1") (pintype "passive"))
      (node (ref "CHV2") (pin "1") (pinfunction "1_1") (pintype "passive"))
      (node (ref "CVH3") (pin "1") (pinfunction "1_1") (pintype "passive"))
      (node (ref "CVH4") (pin "1") (pinfunction "1_1") (pintype "passive"))
      (node (ref "DBOOT1") (pin "C") (pinfunction "C_C") (pintype "passive"))
      (node (ref "DOV3") (pin "A") (pinfunction "A_A") (pintype "passive"))
      (node (ref "DRVR_X") (pin "8") (pinfunction "8/VBOOT_8") (pintype "bidirectional"))
      (node (ref "J_BATT/GND") (pin "1") (pinfunction "1_1") (pintype "passive"))
      (node (ref "J_BATT/GND") (pin "2") (pinfunction "2_2") (pintype "passive"))
      (node (ref "J_BATT/GND") (pin "3") (pinfunction "3_3") (pintype "passive"))
      (node (ref "J_BATT/GND") (pin "4") (pinfunction "4_4") (pintype "passive"))
      (node (ref "QA_H5") (pin "2") (pinfunction "D_2") (pintype "bidirectional"))
      (node (ref "QA_H6") (pin "2") (pinfunction "D_2") (pintype "bidirectional"))
      (node (ref "RLD1") (pin "2") (pinfunction "2_2") (pintype "passive"))
    )
    (net (code "33") (name "VSS_A") (class "Default")
      (node (ref "CBOOT1") (pin "2") (pinfunction "2_2") (pintype "passive"))
      (node (ref "DOV4") (pin "A") (pinfunction "A_A") (pintype "passive"))
      (node (ref "DRVR_X") (pin "6") (pinfunction "6/BRIDGE_6") (pintype "bidirectional"))
      (node (ref "DZ15V2") (pin "2") (pinfunction "A_2") (pintype "passive"))
      (node (ref "J_-VLOAD") (pin "1") (pinfunction "1_1") (pintype "passive"))
      (node (ref "J_-VLOAD") (pin "2") (pinfunction "2_2") (pintype "passive"))
      (node (ref "J_-VLOAD") (pin "3") (pinfunction "3_3") (pintype "passive"))
      (node (ref "J_-VLOAD") (pin "4") (pinfunction "4_4") (pintype "passive"))
      (node (ref "QA_H5") (pin "3") (pinfunction "S_3") (pintype "bidirectional"))
      (node (ref "QA_H6") (pin "3") (pinfunction "S_3") (pintype "bidirectional"))
      (node (ref "QA_L5") (pin "2") (pinfunction "D_2") (pintype "bidirectional"))
      (node (ref "QA_L6") (pin "2") (pinfunction "D_2") (pintype "bidirectional"))
      (node (ref "RGS7") (pin "2") (pinfunction "2_2") (pintype "passive"))
      (node (ref "RGS8") (pin "2") (pinfunction "2_2") (pintype "passive"))
    )
    (net (code "34") (name "_+12DRV") (class "Default")
      (node (ref "D12IN") (pin "A") (pinfunction "A_A") (pintype "passive"))
      (node (ref "J_BATT/GND") (pin "11") (pinfunction "11_11") (pintype "passive"))
    )
    (net (code "35") (name "unconnected-(J_-VLOAD-Pad5)") (class "Default")
      (node (ref "J_-VLOAD") (pin "5") (pinfunction "5_5") (pintype "passive"))
    )
    (net (code "36") (name "unconnected-(J_-VLOAD-Pad6)") (class "Default")
      (node (ref "J_-VLOAD") (pin "6") (pinfunction "6_6") (pintype "passive"))
    )
    (net (code "37") (name "unconnected-(J_-VLOAD-Pad7)") (class "Default")
      (node (ref "J_-VLOAD") (pin "7") (pinfunction "7_7") (pintype "passive"))
    )
    (net (code "38") (name "unconnected-(J_-VLOAD-Pad8)") (class "Default")
      (node (ref "J_-VLOAD") (pin "8") (pinfunction "8_8") (pintype "passive"))
    )
    (net (code "39") (name "unconnected-(J_BATT/GND-Pad5)") (class "Default")
      (node (ref "J_BATT/GND") (pin "5") (pinfunction "5_5") (pintype "passive"))
    )
    (net (code "40") (name "unconnected-(J_BATT/GND-Pad6)") (class "Default")
      (node (ref "J_BATT/GND") (pin "6") (pinfunction "6_6") (pintype "passive"))
    )
    (net (code "41") (name "unconnected-(MS1-Pad1)") (class "Default")
      (node (ref "MS1") (pin "1") (pinfunction "1_1") (pintype "passive"))
    )
    (net (code "42") (name "unconnected-(MS2-Pad1)") (class "Default")
      (node (ref "MS2") (pin "1") (pinfunction "1_1") (pintype "passive"))
    )
    (net (code "43") (name "unconnected-(MS3-Pad1)") (class "Default")
      (node (ref "MS3") (pin "1") (pinfunction "1_1") (pintype "passive"))
    )
  )
)
